# usb_connectors.net
KiCad netlist of a schematic drawn in Altium Designer
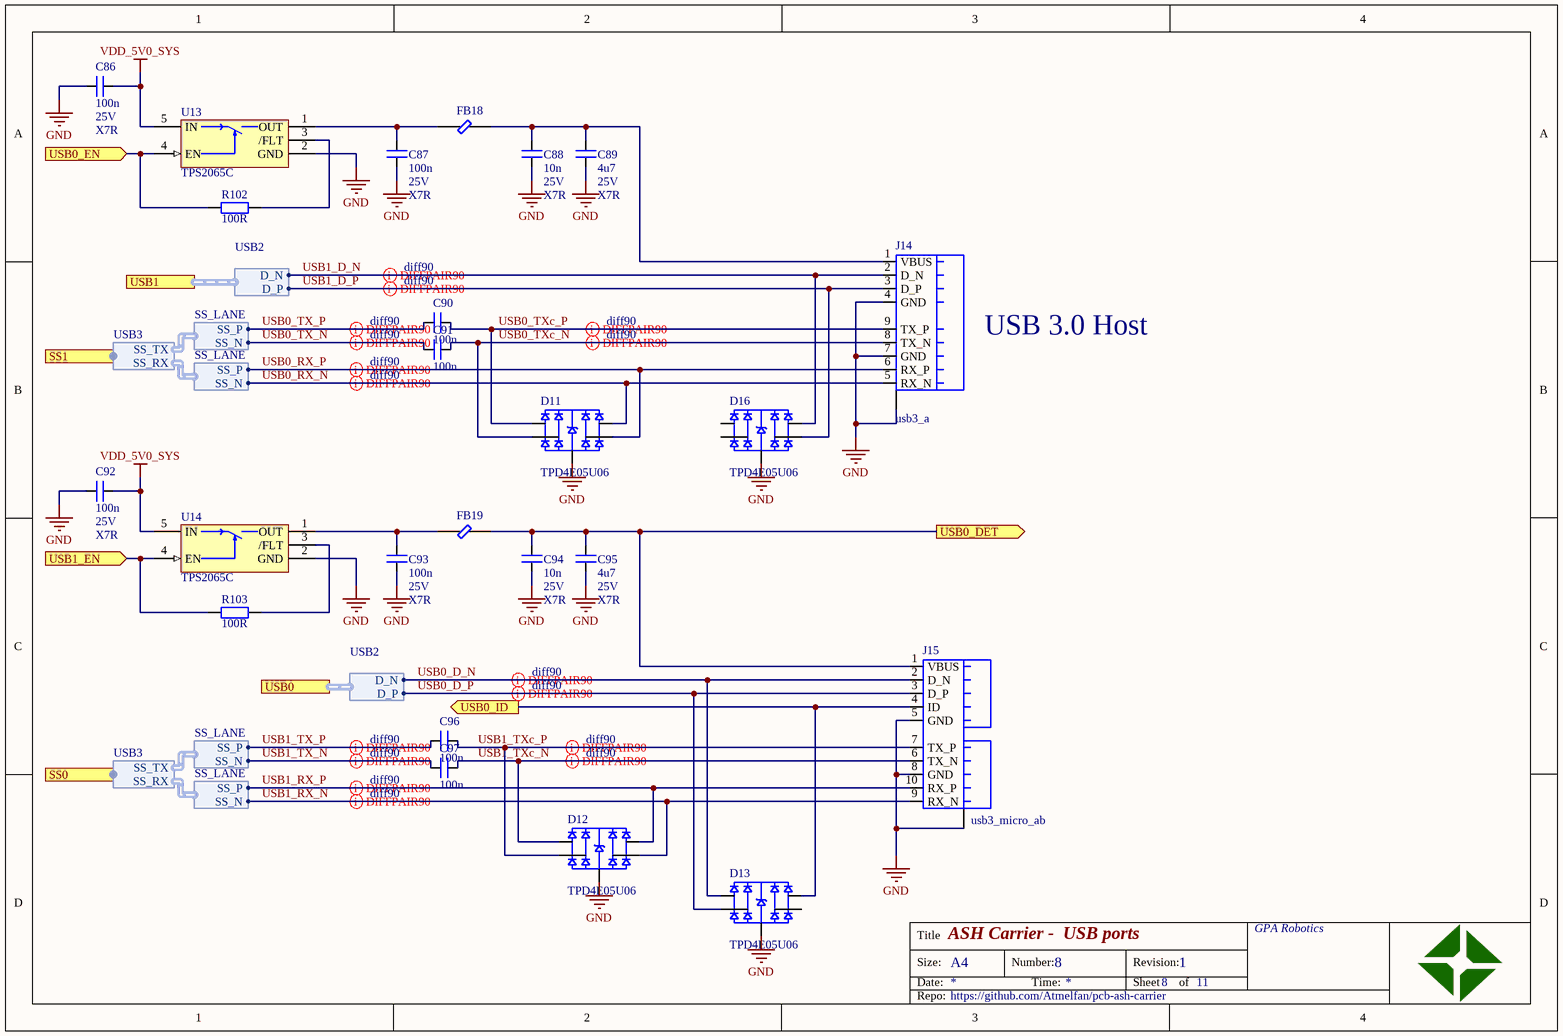
[diagram p0: usb_connectors.SchDoc]

(export (version "E")
  (design (tool "Eeschema 10.0.6"))
  (components
    (comp (ref "C86")
      (value "100n")
      (footprint "C1005[0402]")
      (description "Capacitor")
      (fields (field (name "VOLTAGE") "25V") (field (name "TYPE") "X7R") (field (name "Comment") "cap"))
      (libsource (lib "gpa_passives") (part "cap"))
    )
    (comp (ref "C87")
      (value "100n")
      (footprint "C1005[0402]")
      (description "Capacitor")
      (fields (field (name "VOLTAGE") "25V") (field (name "TYPE") "X7R") (field (name "Comment") "cap"))
      (libsource (lib "gpa_passives") (part "cap"))
    )
    (comp (ref "C88")
      (value "10n")
      (footprint "C1005[0402]")
      (description "Capacitor")
      (fields (field (name "VOLTAGE") "25V") (field (name "TYPE") "X7R") (field (name "Comment") "cap"))
      (libsource (lib "gpa_passives") (part "cap"))
    )
    (comp (ref "C89")
      (value "4u7")
      (footprint "C3216[1206]")
      (description "Capacitor")
      (fields (field (name "VOLTAGE") "25V") (field (name "TYPE") "X7R") (field (name "Comment") "cap"))
      (libsource (lib "gpa_passives") (part "cap"))
    )
    (comp (ref "C90")
      (value "100n")
      (footprint "C1005[0402]")
      (description "Capacitor")
      (fields (field (name "VOLTAGE") "25V") (field (name "Comment") "cap"))
      (libsource (lib "gpa_passives") (part "cap"))
    )
    (comp (ref "C91")
      (value "100n")
      (footprint "C1005[0402]")
      (description "Capacitor")
      (fields (field (name "VOLTAGE") "25V") (field (name "Comment") "cap"))
      (libsource (lib "gpa_passives") (part "cap"))
    )
    (comp (ref "C92")
      (value "100n")
      (footprint "C1005[0402]")
      (description "Capacitor")
      (fields (field (name "VOLTAGE") "25V") (field (name "TYPE") "X7R") (field (name "Comment") "cap"))
      (libsource (lib "gpa_passives") (part "cap"))
    )
    (comp (ref "C93")
      (value "100n")
      (footprint "C1005[0402]")
      (description "Capacitor")
      (fields (field (name "VOLTAGE") "25V") (field (name "TYPE") "X7R") (field (name "Comment") "cap"))
      (libsource (lib "gpa_passives") (part "cap"))
    )
    (comp (ref "C94")
      (value "10n")
      (footprint "C1005[0402]")
      (description "Capacitor")
      (fields (field (name "VOLTAGE") "25V") (field (name "TYPE") "X7R") (field (name "Comment") "cap"))
      (libsource (lib "gpa_passives") (part "cap"))
    )
    (comp (ref "C95")
      (value "4u7")
      (footprint "C3216[1206]")
      (description "Capacitor")
      (fields (field (name "VOLTAGE") "25V") (field (name "TYPE") "X7R") (field (name "Comment") "cap"))
      (libsource (lib "gpa_passives") (part "cap"))
    )
    (comp (ref "C96")
      (value "100n")
      (footprint "C1005[0402]")
      (description "Capacitor")
      (fields (field (name "VOLTAGE") "25V") (field (name "Comment") "cap"))
      (libsource (lib "gpa_passives") (part "cap"))
    )
    (comp (ref "C97")
      (value "100n")
      (footprint "C1005[0402]")
      (description "Capacitor")
      (fields (field (name "VOLTAGE") "25V") (field (name "Comment") "cap"))
      (libsource (lib "gpa_passives") (part "cap"))
    )
    (comp (ref "D11")
      (value "TPD4E05U06")
      (footprint "TI_PSON50P100X55-10N")
      (libsource (lib "gpa_ti") (part "tpd4e05u06"))
    )
    (comp (ref "D12")
      (value "TPD4E05U06")
      (footprint "TI_PSON50P100X55-10N")
      (libsource (lib "gpa_ti") (part "tpd4e05u06"))
    )
    (comp (ref "D13")
      (value "TPD4E05U06")
      (footprint "TI_PSON50P100X55-10N")
      (libsource (lib "gpa_ti") (part "tpd4e05u06"))
    )
    (comp (ref "D16")
      (value "TPD4E05U06")
      (footprint "TI_PSON50P100X55-10N")
      (libsource (lib "gpa_ti") (part "tpd4e05u06"))
    )
    (comp (ref "FB18")
      (value "2506036007Y3")
      (footprint "FBC1608X07N")
      (description "Ferrite bead")
      (libsource (lib "gpa_passives") (part "ferrite_bead"))
    )
    (comp (ref "FB19")
      (value "2506036007Y3")
      (footprint "FBC1608X07N")
      (description "Ferrite bead")
      (libsource (lib "gpa_passives") (part "ferrite_bead"))
    )
    (comp (ref "J14")
      (value "usb3_a")
      (footprint "usb3_a")
      (libsource (lib "gpa_connectors") (part "usb3_a"))
    )
    (comp (ref "J15")
      (value "usb3_micro_ab")
      (footprint "usb3_micro_ab")
      (libsource (lib "gpa_connectors") (part "usb3_micro_ab"))
    )
    (comp (ref "R102")
      (value "100R")
      (footprint "R1005[0402]")
      (description "Resistor")
      (fields (field (name "Comment") "res"))
      (libsource (lib "gpa_passives") (part "res"))
    )
    (comp (ref "R103")
      (value "100R")
      (footprint "R1005[0402]")
      (description "Resistor")
      (fields (field (name "Comment") "res"))
      (libsource (lib "gpa_passives") (part "res"))
    )
    (comp (ref "U13")
      (value "TPS2065C")
      (footprint "TI_SOT95P280X145-5N")
      (libsource (lib "gpa_ti") (part "tps2065c"))
    )
    (comp (ref "U14")
      (value "TPS2065C")
      (footprint "TI_SOT95P280X145-5N")
      (libsource (lib "gpa_ti") (part "tps2065c"))
    )
  )
  (nets
    (net (code "7") (name "/USB0_DET") (class "Default")
      (node (ref "C94") (pin "2") (pinfunction "2_2") (pintype "passive"))
      (node (ref "C95") (pin "2") (pinfunction "2_2") (pintype "passive"))
      (node (ref "FB19") (pin "2") (pinfunction "2_2") (pintype "passive"))
      (node (ref "J15") (pin "1") (pinfunction "VBUS_1") (pintype "passive"))
    )
    (net (code "8") (name "/USB0_D_N") (class "Default")
      (node (ref "D13") (pin "1") (pinfunction "D1+_1") (pintype "passive"))
      (node (ref "J15") (pin "2") (pinfunction "D_N_2") (pintype "passive"))
    )
    (net (code "9") (name "/USB0_D_P") (class "Default")
      (node (ref "D13") (pin "2") (pinfunction "D1-_2") (pintype "passive"))
      (node (ref "J15") (pin "3") (pinfunction "D_P_3") (pintype "passive"))
    )
    (net (code "10") (name "/USB0_EN") (class "Default")
      (node (ref "R102") (pin "1") (pinfunction "1_1") (pintype "passive"))
      (node (ref "U13") (pin "4") (pinfunction "EN_4") (pintype "input"))
    )
    (net (code "11") (name "/USB0_ID") (class "Default")
      (node (ref "D13") (pin "5") (pinfunction "D2+_5") (pintype "passive"))
      (node (ref "J15") (pin "4") (pinfunction "ID_4") (pintype "passive"))
    )
    (net (code "12") (name "/USB0_RX_N") (class "Default")
      (node (ref "D11") (pin "5") (pinfunction "D2+_5") (pintype "passive"))
      (node (ref "J14") (pin "5") (pinfunction "RX_N_5") (pintype "passive"))
    )
    (net (code "13") (name "/USB0_RX_P") (class "Default")
      (node (ref "D11") (pin "4") (pinfunction "D2-_4") (pintype "passive"))
      (node (ref "J14") (pin "6") (pinfunction "RX_P_6") (pintype "passive"))
    )
    (net (code "14") (name "/USB0_TX_N") (class "Default")
      (node (ref "C91") (pin "2") (pinfunction "2_2") (pintype "passive"))
    )
    (net (code "15") (name "/USB0_TX_P") (class "Default")
      (node (ref "C90") (pin "2") (pinfunction "2_2") (pintype "passive"))
    )
    (net (code "16") (name "/USB0_TXc_N") (class "Default")
      (node (ref "C91") (pin "1") (pinfunction "1_1") (pintype "passive"))
      (node (ref "D11") (pin "2") (pinfunction "D1-_2") (pintype "passive"))
      (node (ref "J14") (pin "8") (pinfunction "TX_N_8") (pintype "passive"))
    )
    (net (code "17") (name "/USB0_TXc_P") (class "Default")
      (node (ref "C90") (pin "1") (pinfunction "1_1") (pintype "passive"))
      (node (ref "D11") (pin "1") (pinfunction "D1+_1") (pintype "passive"))
      (node (ref "J14") (pin "9") (pinfunction "TX_P_9") (pintype "passive"))
    )
    (net (code "18") (name "/USB1_D_N") (class "Default")
      (node (ref "D16") (pin "5") (pinfunction "D2+_5") (pintype "passive"))
      (node (ref "J14") (pin "2") (pinfunction "D_N_2") (pintype "passive"))
    )
    (net (code "19") (name "/USB1_D_P") (class "Default")
      (node (ref "D16") (pin "4") (pinfunction "D2-_4") (pintype "passive"))
      (node (ref "J14") (pin "3") (pinfunction "D_P_3") (pintype "passive"))
    )
    (net (code "20") (name "/USB1_EN") (class "Default")
      (node (ref "R103") (pin "1") (pinfunction "1_1") (pintype "passive"))
      (node (ref "U14") (pin "4") (pinfunction "EN_4") (pintype "input"))
    )
    (net (code "21") (name "/USB1_RX_N") (class "Default")
      (node (ref "D12") (pin "4") (pinfunction "D2-_4") (pintype "passive"))
      (node (ref "J15") (pin "9") (pinfunction "RX_N_9") (pintype "passive"))
    )
    (net (code "22") (name "/USB1_RX_P") (class "Default")
      (node (ref "D12") (pin "5") (pinfunction "D2+_5") (pintype "passive"))
      (node (ref "J15") (pin "10") (pinfunction "RX_P_10") (pintype "passive"))
    )
    (net (code "23") (name "/USB1_TX_N") (class "Default")
      (node (ref "C97") (pin "2") (pinfunction "2_2") (pintype "passive"))
    )
    (net (code "24") (name "/USB1_TX_P") (class "Default")
      (node (ref "C96") (pin "2") (pinfunction "2_2") (pintype "passive"))
    )
    (net (code "25") (name "/USB1_TXc_N") (class "Default")
      (node (ref "C97") (pin "1") (pinfunction "1_1") (pintype "passive"))
      (node (ref "D12") (pin "1") (pinfunction "D1+_1") (pintype "passive"))
      (node (ref "J15") (pin "6") (pinfunction "TX_N_6") (pintype "passive"))
    )
    (net (code "26") (name "/USB1_TXc_P") (class "Default")
      (node (ref "C96") (pin "1") (pinfunction "1_1") (pintype "passive"))
      (node (ref "D12") (pin "2") (pinfunction "D1-_2") (pintype "passive"))
      (node (ref "J15") (pin "7") (pinfunction "TX_P_7") (pintype "passive"))
    )
    (net (code "29") (name "GND") (class "Default")
      (node (ref "C86") (pin "2") (pinfunction "2_2") (pintype "passive"))
      (node (ref "C87") (pin "1") (pinfunction "1_1") (pintype "passive"))
      (node (ref "C88") (pin "1") (pinfunction "1_1") (pintype "passive"))
      (node (ref "C89") (pin "1") (pinfunction "1_1") (pintype "passive"))
      (node (ref "C92") (pin "2") (pinfunction "2_2") (pintype "passive"))
      (node (ref "C93") (pin "1") (pinfunction "1_1") (pintype "passive"))
      (node (ref "C94") (pin "1") (pinfunction "1_1") (pintype "passive"))
      (node (ref "C95") (pin "1") (pinfunction "1_1") (pintype "passive"))
      (node (ref "D11") (pin "3") (pinfunction "GND_3") (pintype "passive"))
      (node (ref "D12") (pin "3") (pinfunction "GND_3") (pintype "passive"))
      (node (ref "D13") (pin "3") (pinfunction "GND_3") (pintype "passive"))
      (node (ref "D16") (pin "3") (pinfunction "GND_3") (pintype "passive"))
      (node (ref "J14") (pin "4") (pinfunction "GND_4") (pintype "passive"))
      (node (ref "J14") (pin "7") (pinfunction "GND_7") (pintype "passive"))
      (node (ref "J14") (pin "SHIELD") (pinfunction "SHIELD_SHIELD") (pintype "passive"))
      (node (ref "J15") (pin "5") (pinfunction "GND_5") (pintype "passive"))
      (node (ref "J15") (pin "8") (pinfunction "GND_8") (pintype "passive"))
      (node (ref "J15") (pin "SHIELD") (pinfunction "SHIELD_SHIELD") (pintype "passive"))
      (node (ref "U13") (pin "2") (pinfunction "GND_2") (pintype "power_in"))
      (node (ref "U14") (pin "2") (pinfunction "GND_2") (pintype "power_in"))
    )
    (net (code "30") (name "Net-(J14-VBUS)") (class "Default")
      (node (ref "C88") (pin "2") (pinfunction "2_2") (pintype "passive"))
      (node (ref "C89") (pin "2") (pinfunction "2_2") (pintype "passive"))
      (node (ref "FB18") (pin "2") (pinfunction "2_2") (pintype "passive"))
      (node (ref "J14") (pin "1") (pinfunction "VBUS_1") (pintype "passive"))
    )
    (net (code "31") (name "Net-(U13-OUT)") (class "Default")
      (node (ref "C87") (pin "2") (pinfunction "2_2") (pintype "passive"))
      (node (ref "FB18") (pin "1") (pinfunction "1_1") (pintype "passive"))
      (node (ref "U13") (pin "1") (pinfunction "OUT_1") (pintype "power_in"))
    )
    (net (code "32") (name "Net-(U13-{slash}FLT)") (class "Default")
      (node (ref "R102") (pin "2") (pinfunction "2_2") (pintype "passive"))
      (node (ref "U13") (pin "3") (pinfunction "/FLT_3") (pintype "open_collector"))
    )
    (net (code "33") (name "Net-(U14-OUT)") (class "Default")
      (node (ref "C93") (pin "2") (pinfunction "2_2") (pintype "passive"))
      (node (ref "FB19") (pin "1") (pinfunction "1_1") (pintype "passive"))
      (node (ref "U14") (pin "1") (pinfunction "OUT_1") (pintype "power_in"))
    )
    (net (code "34") (name "Net-(U14-{slash}FLT)") (class "Default")
      (node (ref "R103") (pin "2") (pinfunction "2_2") (pintype "passive"))
      (node (ref "U14") (pin "3") (pinfunction "/FLT_3") (pintype "open_collector"))
    )
    (net (code "35") (name "VDD_5V0_SYS") (class "Default")
      (node (ref "C86") (pin "1") (pinfunction "1_1") (pintype "passive"))
      (node (ref "C92") (pin "1") (pinfunction "1_1") (pintype "passive"))
      (node (ref "U13") (pin "5") (pinfunction "IN_5") (pintype "power_in"))
      (node (ref "U14") (pin "5") (pinfunction "IN_5") (pintype "power_in"))
    )
    (net (code "36") (name "unconnected-(D13-D2--Pad4)") (class "Default")
      (node (ref "D13") (pin "4") (pinfunction "D2-_4") (pintype "passive"))
    )
    (net (code "37") (name "unconnected-(D16-D1+-Pad1)") (class "Default")
      (node (ref "D16") (pin "1") (pinfunction "D1+_1") (pintype "passive"))
    )
    (net (code "38") (name "unconnected-(D16-D1--Pad2)") (class "Default")
      (node (ref "D16") (pin "2") (pinfunction "D1-_2") (pintype "passive"))
    )
  )
)
